# LEDs.net
KiCad netlist of a schematic drawn in Altium Designer
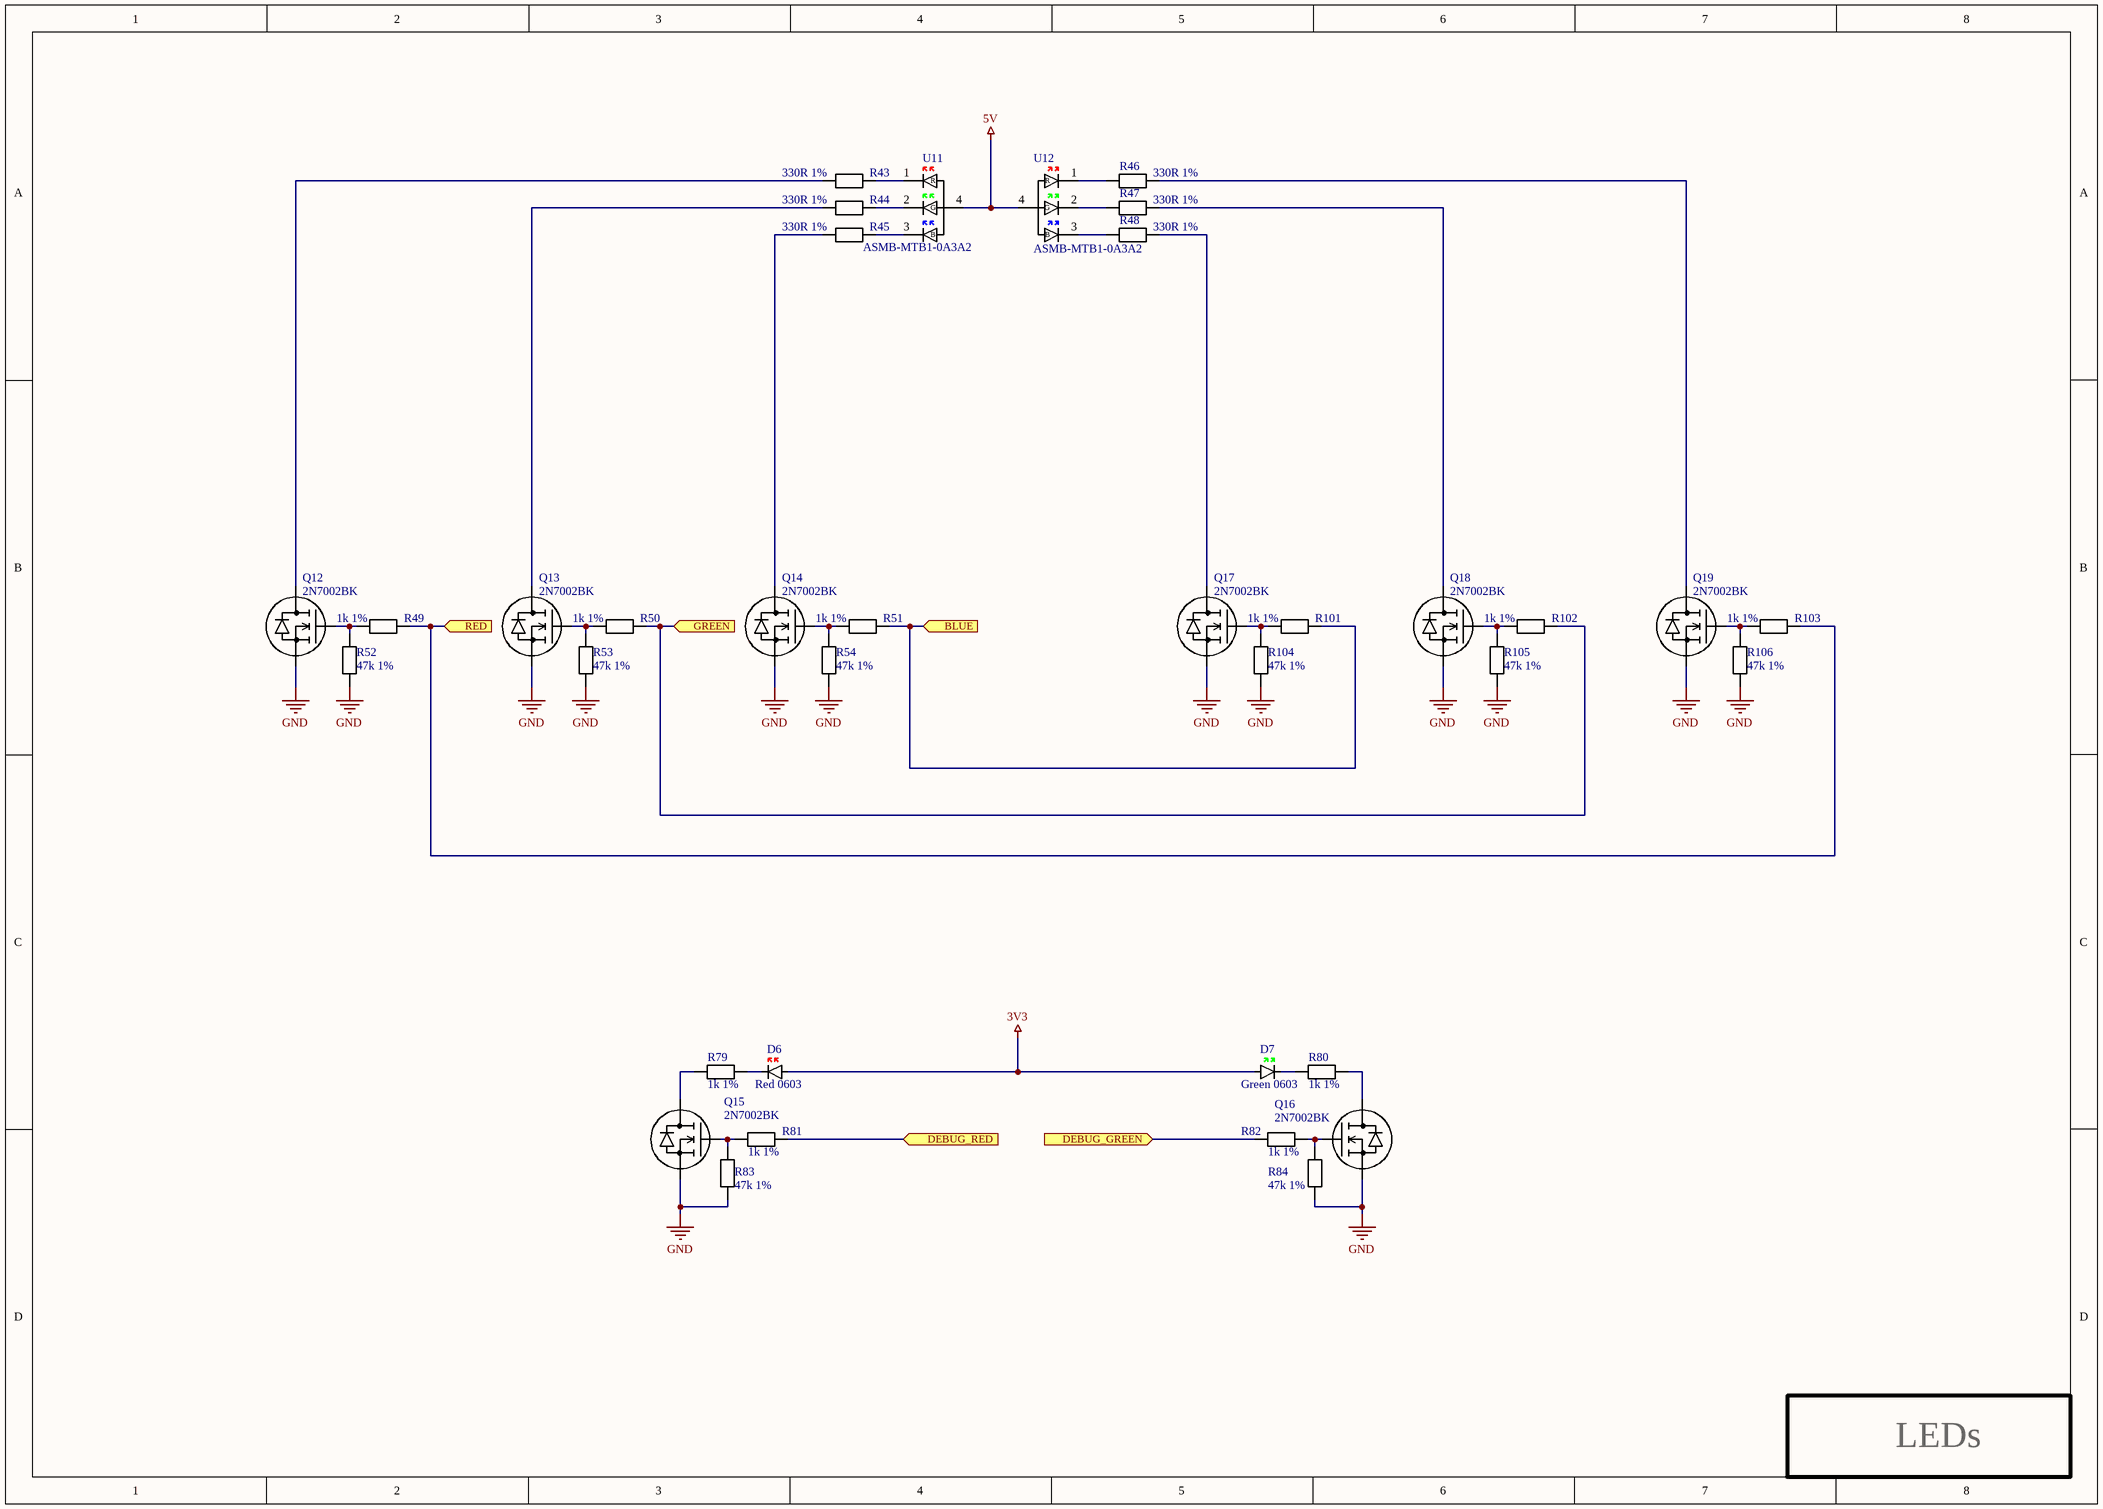
[diagram p0: LEDs.SchDoc]

(export (version "E")
  (design (tool "Eeschema 10.0.6"))
  (components
    (comp (ref "D6")
      (value "Red 0603")
      (footprint "LED_0603_AUTO")
      (description "Generic Red 0603")
      (fields (field (name "MPN") "[Generic]"))
      (libsource (lib "GuowLib") (part "LED_Red_0603"))
    )
    (comp (ref "D7")
      (value "Green 0603")
      (footprint "LED_0603_AUTO")
      (description "Generic Green 0603")
      (fields (field (name "MANUFACTURER") "[Generic]"))
      (libsource (lib "GuowLib") (part "LED_Green_0603"))
    )
    (comp (ref "Q12")
      (value "2N7002BK")
      (footprint "SOT23-3_AUTO")
      (description "60 V, 350 mA N-channel Trench MOSFET Vth=1.6V")
      (fields (field (name "MANUFACTURER") "Nexperia"))
      (libsource (lib "GuowLib") (part "2N7002BK"))
    )
    (comp (ref "Q13")
      (value "2N7002BK")
      (footprint "SOT23-3_AUTO")
      (description "60 V, 350 mA N-channel Trench MOSFET Vth=1.6V")
      (fields (field (name "MANUFACTURER") "Nexperia"))
      (libsource (lib "GuowLib") (part "2N7002BK"))
    )
    (comp (ref "Q14")
      (value "2N7002BK")
      (footprint "SOT23-3_AUTO")
      (description "60 V, 350 mA N-channel Trench MOSFET Vth=1.6V")
      (fields (field (name "MANUFACTURER") "Nexperia"))
      (libsource (lib "GuowLib") (part "2N7002BK"))
    )
    (comp (ref "Q15")
      (value "2N7002BK")
      (footprint "SOT23-3_AUTO")
      (description "60 V, 350 mA N-channel Trench MOSFET Vth=1.6V")
      (fields (field (name "MANUFACTURER") "Nexperia"))
      (libsource (lib "GuowLib") (part "2N7002BK"))
    )
    (comp (ref "Q16")
      (value "2N7002BK")
      (footprint "SOT23-3_AUTO")
      (description "60 V, 350 mA N-channel Trench MOSFET Vth=1.6V")
      (fields (field (name "MANUFACTURER") "Nexperia"))
      (libsource (lib "GuowLib") (part "2N7002BK"))
    )
    (comp (ref "Q17")
      (value "2N7002BK")
      (footprint "SOT23-3_AUTO")
      (description "60 V, 350 mA N-channel Trench MOSFET Vth=1.6V")
      (fields (field (name "MANUFACTURER") "Nexperia"))
      (libsource (lib "GuowLib") (part "2N7002BK"))
    )
    (comp (ref "Q18")
      (value "2N7002BK")
      (footprint "SOT23-3_AUTO")
      (description "60 V, 350 mA N-channel Trench MOSFET Vth=1.6V")
      (fields (field (name "MANUFACTURER") "Nexperia"))
      (libsource (lib "GuowLib") (part "2N7002BK"))
    )
    (comp (ref "Q19")
      (value "2N7002BK")
      (footprint "SOT23-3_AUTO")
      (description "60 V, 350 mA N-channel Trench MOSFET Vth=1.6V")
      (fields (field (name "MANUFACTURER") "Nexperia"))
      (libsource (lib "GuowLib") (part "2N7002BK"))
    )
    (comp (ref "R43")
      (value "330R 1%")
      (footprint "R_0603_AUTO")
      (fields (field (name "MPN") "[Generic]"))
      (libsource (lib "GuowLib") (part "Resistor"))
    )
    (comp (ref "R44")
      (value "330R 1%")
      (footprint "R_0603_AUTO")
      (fields (field (name "MPN") "[Generic]"))
      (libsource (lib "GuowLib") (part "Resistor"))
    )
    (comp (ref "R45")
      (value "330R 1%")
      (footprint "R_0603_AUTO")
      (fields (field (name "MPN") "[Generic]"))
      (libsource (lib "GuowLib") (part "Resistor"))
    )
    (comp (ref "R46")
      (value "330R 1%")
      (footprint "R_0603_AUTO")
      (fields (field (name "MPN") "[Generic]"))
      (libsource (lib "") (part "Resistor_2"))
    )
    (comp (ref "R47")
      (value "330R 1%")
      (footprint "R_0603_AUTO")
      (fields (field (name "MPN") "[Generic]"))
      (libsource (lib "") (part "Resistor_2"))
    )
    (comp (ref "R48")
      (value "330R 1%")
      (footprint "R_0603_AUTO")
      (fields (field (name "MPN") "[Generic]"))
      (libsource (lib "") (part "Resistor_2"))
    )
    (comp (ref "R49")
      (value "1k 1%")
      (footprint "R_0603_AUTO")
      (fields (field (name "MPN") "[Generic]"))
      (libsource (lib "GuowLib") (part "Resistor"))
    )
    (comp (ref "R50")
      (value "1k 1%")
      (footprint "R_0603_AUTO")
      (fields (field (name "MPN") "[Generic]"))
      (libsource (lib "GuowLib") (part "Resistor"))
    )
    (comp (ref "R51")
      (value "1k 1%")
      (footprint "R_0603_AUTO")
      (fields (field (name "MPN") "[Generic]"))
      (libsource (lib "GuowLib") (part "Resistor"))
    )
    (comp (ref "R52")
      (value "47k 1%")
      (footprint "R_0603_AUTO")
      (fields (field (name "MPN") "[Generic]"))
      (libsource (lib "") (part "Resistor_1"))
    )
    (comp (ref "R53")
      (value "47k 1%")
      (footprint "R_0603_AUTO")
      (fields (field (name "MPN") "[Generic]"))
      (libsource (lib "") (part "Resistor_1"))
    )
    (comp (ref "R54")
      (value "47k 1%")
      (footprint "R_0603_AUTO")
      (fields (field (name "MPN") "[Generic]"))
      (libsource (lib "") (part "Resistor_1"))
    )
    (comp (ref "R79")
      (value "1k 1%")
      (footprint "R_0603_AUTO")
      (fields (field (name "MPN") "[Generic]"))
      (libsource (lib "GuowLib") (part "Resistor"))
    )
    (comp (ref "R80")
      (value "1k 1%")
      (footprint "R_0603_AUTO")
      (fields (field (name "MPN") "[Generic]"))
      (libsource (lib "") (part "Resistor_3"))
    )
    (comp (ref "R81")
      (value "1k 1%")
      (footprint "R_0603_AUTO")
      (fields (field (name "MPN") "[Generic]"))
      (libsource (lib "") (part "Resistor_3"))
    )
    (comp (ref "R82")
      (value "1k 1%")
      (footprint "R_0603_AUTO")
      (fields (field (name "MPN") "[Generic]"))
      (libsource (lib "") (part "Resistor_3"))
    )
    (comp (ref "R83")
      (value "47k 1%")
      (footprint "R_0603_AUTO")
      (fields (field (name "MPN") "[Generic]"))
      (libsource (lib "") (part "Resistor_1"))
    )
    (comp (ref "R84")
      (value "47k 1%")
      (footprint "R_0603_AUTO")
      (fields (field (name "MPN") "[Generic]"))
      (libsource (lib "") (part "Resistor_1"))
    )
    (comp (ref "R101")
      (value "1k 1%")
      (footprint "R_0603_AUTO")
      (fields (field (name "MPN") "[Generic]"))
      (libsource (lib "GuowLib") (part "Resistor"))
    )
    (comp (ref "R102")
      (value "1k 1%")
      (footprint "R_0603_AUTO")
      (fields (field (name "MPN") "[Generic]"))
      (libsource (lib "GuowLib") (part "Resistor"))
    )
    (comp (ref "R103")
      (value "1k 1%")
      (footprint "R_0603_AUTO")
      (fields (field (name "MPN") "[Generic]"))
      (libsource (lib "GuowLib") (part "Resistor"))
    )
    (comp (ref "R104")
      (value "47k 1%")
      (footprint "R_0603_AUTO")
      (fields (field (name "MPN") "[Generic]"))
      (libsource (lib "") (part "Resistor_1"))
    )
    (comp (ref "R105")
      (value "47k 1%")
      (footprint "R_0603_AUTO")
      (fields (field (name "MPN") "[Generic]"))
      (libsource (lib "") (part "Resistor_1"))
    )
    (comp (ref "R106")
      (value "47k 1%")
      (footprint "R_0603_AUTO")
      (fields (field (name "MPN") "[Generic]"))
      (libsource (lib "") (part "Resistor_1"))
    )
    (comp (ref "U11")
      (value "ASMB-MTB1-0A3A2")
      (footprint "PLCC4")
      (description "LED RGB DIFFUSED 4PLCC SMD")
      (fields (field (name "MANUFACTURER") "Broadcom Limited"))
      (libsource (lib "GuowLib") (part "ASMB-MTB1-0A3A2"))
    )
    (comp (ref "U12")
      (value "ASMB-MTB1-0A3A2")
      (footprint "PLCC4")
      (description "LED RGB DIFFUSED 4PLCC SMD")
      (fields (field (name "MANUFACTURER") "Broadcom Limited"))
      (libsource (lib "GuowLib") (part "ASMB-MTB1-0A3A2"))
    )
  )
  (nets
    (net (code "1") (name "/BLUE") (class "Default")
      (node (ref "R101") (pin "1") (pinfunction "1_1") (pintype "passive"))
      (node (ref "R51") (pin "1") (pinfunction "1_1") (pintype "passive"))
    )
    (net (code "2") (name "/DEBUG_GREEN") (class "Default")
      (node (ref "R82") (pin "1") (pinfunction "1_1") (pintype "passive"))
    )
    (net (code "3") (name "/DEBUG_RED") (class "Default")
      (node (ref "R81") (pin "2") (pinfunction "2_2") (pintype "passive"))
    )
    (net (code "4") (name "/GREEN") (class "Default")
      (node (ref "R102") (pin "1") (pinfunction "1_1") (pintype "passive"))
      (node (ref "R50") (pin "1") (pinfunction "1_1") (pintype "passive"))
    )
    (net (code "5") (name "/RED") (class "Default")
      (node (ref "R103") (pin "1") (pinfunction "1_1") (pintype "passive"))
      (node (ref "R49") (pin "1") (pinfunction "1_1") (pintype "passive"))
    )
    (net (code "6") (name "3V3") (class "Default")
      (node (ref "D6") (pin "2") (pinfunction "A_2") (pintype "passive"))
      (node (ref "D7") (pin "2") (pinfunction "A_2") (pintype "passive"))
    )
    (net (code "7") (name "5V") (class "Default")
      (node (ref "U11") (pin "4") (pinfunction "4_4") (pintype "passive"))
      (node (ref "U12") (pin "4") (pinfunction "4_4") (pintype "passive"))
    )
    (net (code "8") (name "GND") (class "Default")
      (node (ref "Q12") (pin "2") (pinfunction "S_2") (pintype "passive"))
      (node (ref "Q13") (pin "2") (pinfunction "S_2") (pintype "passive"))
      (node (ref "Q14") (pin "2") (pinfunction "S_2") (pintype "passive"))
      (node (ref "Q15") (pin "2") (pinfunction "S_2") (pintype "passive"))
      (node (ref "Q16") (pin "2") (pinfunction "S_2") (pintype "passive"))
      (node (ref "Q17") (pin "2") (pinfunction "S_2") (pintype "passive"))
      (node (ref "Q18") (pin "2") (pinfunction "S_2") (pintype "passive"))
      (node (ref "Q19") (pin "2") (pinfunction "S_2") (pintype "passive"))
      (node (ref "R104") (pin "2") (pinfunction "2_2") (pintype "passive"))
      (node (ref "R105") (pin "2") (pinfunction "2_2") (pintype "passive"))
      (node (ref "R106") (pin "2") (pinfunction "2_2") (pintype "passive"))
      (node (ref "R52") (pin "2") (pinfunction "2_2") (pintype "passive"))
      (node (ref "R53") (pin "2") (pinfunction "2_2") (pintype "passive"))
      (node (ref "R54") (pin "2") (pinfunction "2_2") (pintype "passive"))
      (node (ref "R83") (pin "2") (pinfunction "2_2") (pintype "passive"))
      (node (ref "R84") (pin "2") (pinfunction "2_2") (pintype "passive"))
    )
    (net (code "9") (name "Net-(D6-C)") (class "Default")
      (node (ref "D6") (pin "1") (pinfunction "C_1") (pintype "passive"))
      (node (ref "R79") (pin "1") (pinfunction "1_1") (pintype "passive"))
    )
    (net (code "10") (name "Net-(D7-C)") (class "Default")
      (node (ref "D7") (pin "1") (pinfunction "C_1") (pintype "passive"))
      (node (ref "R80") (pin "1") (pinfunction "1_1") (pintype "passive"))
    )
    (net (code "11") (name "Net-(Q12-D)") (class "Default")
      (node (ref "Q12") (pin "3") (pinfunction "D_3") (pintype "passive"))
      (node (ref "R43") (pin "2") (pinfunction "2_2") (pintype "passive"))
    )
    (net (code "12") (name "Net-(Q12-G)") (class "Default")
      (node (ref "Q12") (pin "1") (pinfunction "G_1") (pintype "passive"))
      (node (ref "R49") (pin "2") (pinfunction "2_2") (pintype "passive"))
      (node (ref "R52") (pin "1") (pinfunction "1_1") (pintype "passive"))
    )
    (net (code "13") (name "Net-(Q13-D)") (class "Default")
      (node (ref "Q13") (pin "3") (pinfunction "D_3") (pintype "passive"))
      (node (ref "R44") (pin "2") (pinfunction "2_2") (pintype "passive"))
    )
    (net (code "14") (name "Net-(Q13-G)") (class "Default")
      (node (ref "Q13") (pin "1") (pinfunction "G_1") (pintype "passive"))
      (node (ref "R50") (pin "2") (pinfunction "2_2") (pintype "passive"))
      (node (ref "R53") (pin "1") (pinfunction "1_1") (pintype "passive"))
    )
    (net (code "15") (name "Net-(Q14-D)") (class "Default")
      (node (ref "Q14") (pin "3") (pinfunction "D_3") (pintype "passive"))
      (node (ref "R45") (pin "2") (pinfunction "2_2") (pintype "passive"))
    )
    (net (code "16") (name "Net-(Q14-G)") (class "Default")
      (node (ref "Q14") (pin "1") (pinfunction "G_1") (pintype "passive"))
      (node (ref "R51") (pin "2") (pinfunction "2_2") (pintype "passive"))
      (node (ref "R54") (pin "1") (pinfunction "1_1") (pintype "passive"))
    )
    (net (code "17") (name "Net-(Q15-D)") (class "Default")
      (node (ref "Q15") (pin "3") (pinfunction "D_3") (pintype "passive"))
      (node (ref "R79") (pin "2") (pinfunction "2_2") (pintype "passive"))
    )
    (net (code "18") (name "Net-(Q15-G)") (class "Default")
      (node (ref "Q15") (pin "1") (pinfunction "G_1") (pintype "passive"))
      (node (ref "R81") (pin "1") (pinfunction "1_1") (pintype "passive"))
      (node (ref "R83") (pin "1") (pinfunction "1_1") (pintype "passive"))
    )
    (net (code "19") (name "Net-(Q16-D)") (class "Default")
      (node (ref "Q16") (pin "3") (pinfunction "D_3") (pintype "passive"))
      (node (ref "R80") (pin "2") (pinfunction "2_2") (pintype "passive"))
    )
    (net (code "20") (name "Net-(Q16-G)") (class "Default")
      (node (ref "Q16") (pin "1") (pinfunction "G_1") (pintype "passive"))
      (node (ref "R82") (pin "2") (pinfunction "2_2") (pintype "passive"))
      (node (ref "R84") (pin "1") (pinfunction "1_1") (pintype "passive"))
    )
    (net (code "21") (name "Net-(Q17-D)") (class "Default")
      (node (ref "Q17") (pin "3") (pinfunction "D_3") (pintype "passive"))
      (node (ref "R48") (pin "2") (pinfunction "2_2") (pintype "passive"))
    )
    (net (code "22") (name "Net-(Q17-G)") (class "Default")
      (node (ref "Q17") (pin "1") (pinfunction "G_1") (pintype "passive"))
      (node (ref "R101") (pin "2") (pinfunction "2_2") (pintype "passive"))
      (node (ref "R104") (pin "1") (pinfunction "1_1") (pintype "passive"))
    )
    (net (code "23") (name "Net-(Q18-D)") (class "Default")
      (node (ref "Q18") (pin "3") (pinfunction "D_3") (pintype "passive"))
      (node (ref "R47") (pin "2") (pinfunction "2_2") (pintype "passive"))
    )
    (net (code "24") (name "Net-(Q18-G)") (class "Default")
      (node (ref "Q18") (pin "1") (pinfunction "G_1") (pintype "passive"))
      (node (ref "R102") (pin "2") (pinfunction "2_2") (pintype "passive"))
      (node (ref "R105") (pin "1") (pinfunction "1_1") (pintype "passive"))
    )
    (net (code "25") (name "Net-(Q19-D)") (class "Default")
      (node (ref "Q19") (pin "3") (pinfunction "D_3") (pintype "passive"))
      (node (ref "R46") (pin "2") (pinfunction "2_2") (pintype "passive"))
    )
    (net (code "26") (name "Net-(Q19-G)") (class "Default")
      (node (ref "Q19") (pin "1") (pinfunction "G_1") (pintype "passive"))
      (node (ref "R103") (pin "2") (pinfunction "2_2") (pintype "passive"))
      (node (ref "R106") (pin "1") (pinfunction "1_1") (pintype "passive"))
    )
    (net (code "27") (name "Net-(U11-B)") (class "Default")
      (node (ref "R45") (pin "1") (pinfunction "1_1") (pintype "passive"))
      (node (ref "U11") (pin "3") (pinfunction "B_3") (pintype "passive"))
    )
    (net (code "28") (name "Net-(U11-G)") (class "Default")
      (node (ref "R44") (pin "1") (pinfunction "1_1") (pintype "passive"))
      (node (ref "U11") (pin "2") (pinfunction "G_2") (pintype "passive"))
    )
    (net (code "29") (name "Net-(U11-R)") (class "Default")
      (node (ref "R43") (pin "1") (pinfunction "1_1") (pintype "passive"))
      (node (ref "U11") (pin "1") (pinfunction "R_1") (pintype "passive"))
    )
    (net (code "30") (name "Net-(U12-B)") (class "Default")
      (node (ref "R48") (pin "1") (pinfunction "1_1") (pintype "passive"))
      (node (ref "U12") (pin "3") (pinfunction "B_3") (pintype "passive"))
    )
    (net (code "31") (name "Net-(U12-G)") (class "Default")
      (node (ref "R47") (pin "1") (pinfunction "1_1") (pintype "passive"))
      (node (ref "U12") (pin "2") (pinfunction "G_2") (pintype "passive"))
    )
    (net (code "32") (name "Net-(U12-R)") (class "Default")
      (node (ref "R46") (pin "1") (pinfunction "1_1") (pintype "passive"))
      (node (ref "U12") (pin "1") (pinfunction "R_1") (pintype "passive"))
    )
  )
)
